# Stepper_driver.net
KiCad netlist of a schematic drawn in Altium Designer
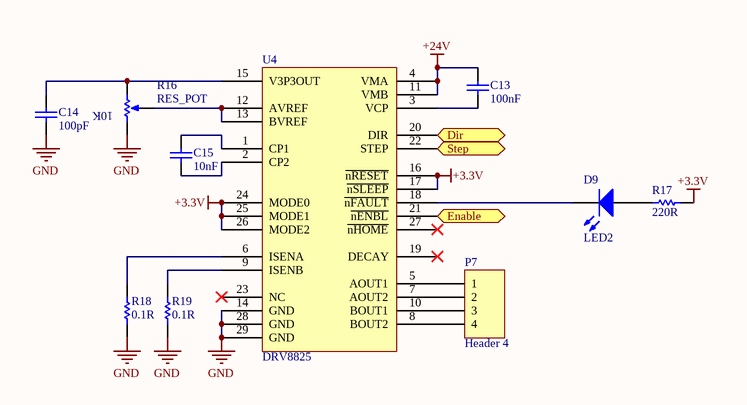
[diagram p0: Stepper_driver.SchDoc]

(export (version "E")
  (design (tool "Eeschema 10.0.6"))
  (components
    (comp (ref "C13")
      (value "100nF")
      (footprint "1608[0603]")
      (description "Capacitor")
      (fields (field (name "Comment") "Cap") (field (name "PUBLISHER") "Altium Limited"))
      (libsource (lib "Schematic Lib") (part "Cap"))
    )
    (comp (ref "C14")
      (value "100pF")
      (footprint "Miscellaneous Devices:1608[0603]")
      (description "Capacitor")
      (fields (field (name "Comment") "Cap") (field (name "PUBLISHER") "Altium Limited"))
      (libsource (lib "Schematic Lib") (part "Cap"))
    )
    (comp (ref "C15")
      (value "10nF")
      (footprint "1608[0603]")
      (description "Capacitor")
      (fields (field (name "Comment") "Cap") (field (name "PUBLISHER") "Altium Limited"))
      (libsource (lib "Schematic Lib") (part "Cap"))
    )
    (comp (ref "D9")
      (value "LED2")
      (footprint "LED 0805")
      (description "Typical RED, GREEN, YELLOW, AMBER GaAs LED")
      (fields (field (name "PUBLISHER") "Altium Limited"))
      (libsource (lib "Miscellaneous Devices") (part "LED2"))
    )
    (comp (ref "P7")
      (value "Header 4")
      (footprint "HDR1X4")
      (description "Header, 4-Pin")
      (fields (field (name "PUBLISHER") "Altium Limited"))
      (libsource (lib "Miscellaneous Connectors") (part "Header 4"))
    )
    (comp (ref "R16") (value "RES_POT") (footprint "RES_SMD") (libsource (lib "Schlib1") (part "RES_POT")))
    (comp (ref "R17")
      (value "220R")
      (footprint "J1-0603")
      (description "Resistor 0805")
      (fields (field (name "Comment") "Res") (field (name "PUBLISHER") "Altium Limited"))
      (libsource (lib "Schematic Lib") (part "Res"))
    )
    (comp (ref "R18")
      (value "0.1R")
      (footprint "C1206")
      (description "Resistor 0805")
      (fields (field (name "Comment") "Res") (field (name "PUBLISHER") "Altium Limited"))
      (libsource (lib "Schematic Lib") (part "Res"))
    )
    (comp (ref "R19")
      (value "0.1R")
      (footprint "C1206")
      (description "Resistor 0805")
      (fields (field (name "Comment") "Res") (field (name "PUBLISHER") "Altium Limited"))
      (libsource (lib "Schematic Lib") (part "Res"))
    )
    (comp (ref "U4") (value "DRV8825") (footprint "DVR") (libsource (lib "Schlib1") (part "DRV8825")))
  )
  (nets
    (net (code "1") (name "+3.3V") (class "Default")
      (node (ref "R17") (pin "2") (pinfunction "2_2") (pintype "passive"))
      (node (ref "U4") (pin "16") (pinfunction "~{nRESET}_16") (pintype "passive"))
      (node (ref "U4") (pin "17") (pinfunction "~{nSLEEP}_17") (pintype "passive"))
      (node (ref "U4") (pin "24") (pinfunction "MODE0_24") (pintype "passive"))
      (node (ref "U4") (pin "25") (pinfunction "MODE1_25") (pintype "passive"))
      (node (ref "U4") (pin "26") (pinfunction "MODE2_26") (pintype "passive"))
    )
    (net (code "2") (name "+24V") (class "Default")
      (node (ref "C13") (pin "2") (pinfunction "2_2") (pintype "passive"))
      (node (ref "U4") (pin "11") (pinfunction "VMB_11") (pintype "passive"))
      (node (ref "U4") (pin "4") (pinfunction "VMA_4") (pintype "passive"))
    )
    (net (code "3") (name "/Dir") (class "Default")
      (node (ref "U4") (pin "20") (pinfunction "DIR_20") (pintype "passive"))
    )
    (net (code "4") (name "/Enable") (class "Default")
      (node (ref "U4") (pin "21") (pinfunction "~{nENBL}_21") (pintype "passive"))
    )
    (net (code "5") (name "/Step") (class "Default")
      (node (ref "U4") (pin "22") (pinfunction "STEP_22") (pintype "passive"))
    )
    (net (code "6") (name "GND") (class "Default")
      (node (ref "C14") (pin "2") (pinfunction "2_2") (pintype "passive"))
      (node (ref "R16") (pin "1") (pinfunction "TOP_1") (pintype "passive"))
      (node (ref "R18") (pin "1") (pinfunction "1_1") (pintype "passive"))
      (node (ref "R19") (pin "1") (pinfunction "1_1") (pintype "passive"))
      (node (ref "U4") (pin "14") (pinfunction "GND_14") (pintype "passive"))
      (node (ref "U4") (pin "28") (pinfunction "GND_28") (pintype "passive"))
      (node (ref "U4") (pin "29") (pinfunction "GND_29") (pintype "passive"))
    )
    (net (code "7") (name "Net-(D9-A)") (class "Default")
      (node (ref "D9") (pin "1") (pinfunction "A_1") (pintype "passive"))
      (node (ref "R17") (pin "1") (pinfunction "1_1") (pintype "passive"))
    )
    (net (code "8") (name "Net-(D9-K)") (class "Default")
      (node (ref "D9") (pin "2") (pinfunction "K_2") (pintype "passive"))
      (node (ref "U4") (pin "18") (pinfunction "~{nFAULT}_18") (pintype "passive"))
    )
    (net (code "9") (name "Net-(R16-BOT)") (class "Default")
      (node (ref "C14") (pin "1") (pinfunction "1_1") (pintype "passive"))
      (node (ref "R16") (pin "2") (pinfunction "BOT_2") (pintype "passive"))
      (node (ref "U4") (pin "15") (pinfunction "V3P3OUT_15") (pintype "passive"))
    )
    (net (code "10") (name "Net-(R16-TAP)") (class "Default")
      (node (ref "R16") (pin "3") (pinfunction "TAP_3") (pintype "passive"))
      (node (ref "U4") (pin "12") (pinfunction "AVREF_12") (pintype "passive"))
      (node (ref "U4") (pin "13") (pinfunction "BVREF_13") (pintype "passive"))
    )
    (net (code "11") (name "Net-(U4-AOUT1)") (class "Default")
      (node (ref "P7") (pin "1") (pinfunction "1_1") (pintype "passive"))
      (node (ref "U4") (pin "5") (pinfunction "AOUT1_5") (pintype "passive"))
    )
    (net (code "12") (name "Net-(U4-AOUT2)") (class "Default")
      (node (ref "P7") (pin "2") (pinfunction "2_2") (pintype "passive"))
      (node (ref "U4") (pin "7") (pinfunction "AOUT2_7") (pintype "passive"))
    )
    (net (code "13") (name "Net-(U4-BOUT1)") (class "Default")
      (node (ref "P7") (pin "3") (pinfunction "3_3") (pintype "passive"))
      (node (ref "U4") (pin "10") (pinfunction "BOUT1_10") (pintype "passive"))
    )
    (net (code "14") (name "Net-(U4-BOUT2)") (class "Default")
      (node (ref "P7") (pin "4") (pinfunction "4_4") (pintype "passive"))
      (node (ref "U4") (pin "8") (pinfunction "BOUT2_8") (pintype "passive"))
    )
    (net (code "15") (name "Net-(U4-CP1)") (class "Default")
      (node (ref "C15") (pin "2") (pinfunction "2_2") (pintype "passive"))
      (node (ref "U4") (pin "1") (pinfunction "CP1_1") (pintype "passive"))
    )
    (net (code "16") (name "Net-(U4-CP2)") (class "Default")
      (node (ref "C15") (pin "1") (pinfunction "1_1") (pintype "passive"))
      (node (ref "U4") (pin "2") (pinfunction "CP2_2") (pintype "passive"))
    )
    (net (code "17") (name "Net-(U4-ISENA)") (class "Default")
      (node (ref "R18") (pin "2") (pinfunction "2_2") (pintype "passive"))
      (node (ref "U4") (pin "6") (pinfunction "ISENA_6") (pintype "passive"))
    )
    (net (code "18") (name "Net-(U4-ISENB)") (class "Default")
      (node (ref "R19") (pin "2") (pinfunction "2_2") (pintype "passive"))
      (node (ref "U4") (pin "9") (pinfunction "ISENB_9") (pintype "passive"))
    )
    (net (code "19") (name "Net-(U4-VCP)") (class "Default")
      (node (ref "C13") (pin "1") (pinfunction "1_1") (pintype "passive"))
      (node (ref "U4") (pin "3") (pinfunction "VCP_3") (pintype "passive"))
    )
    (net (code "20") (name "unconnected-(U4-DECAY-Pad19)") (class "Default")
      (node (ref "U4") (pin "19") (pinfunction "DECAY_19") (pintype "passive+no_connect"))
    )
    (net (code "21") (name "unconnected-(U4-NC-Pad23)") (class "Default")
      (node (ref "U4") (pin "23") (pinfunction "NC_23") (pintype "passive+no_connect"))
    )
    (net (code "22") (name "unconnected-(U4-~{nHOME}-Pad27)") (class "Default")
      (node (ref "U4") (pin "27") (pinfunction "~{nHOME}_27") (pintype "passive+no_connect"))
    )
  )
)
